# tiny85.net
KiCad netlist of a schematic drawn in EAGLE
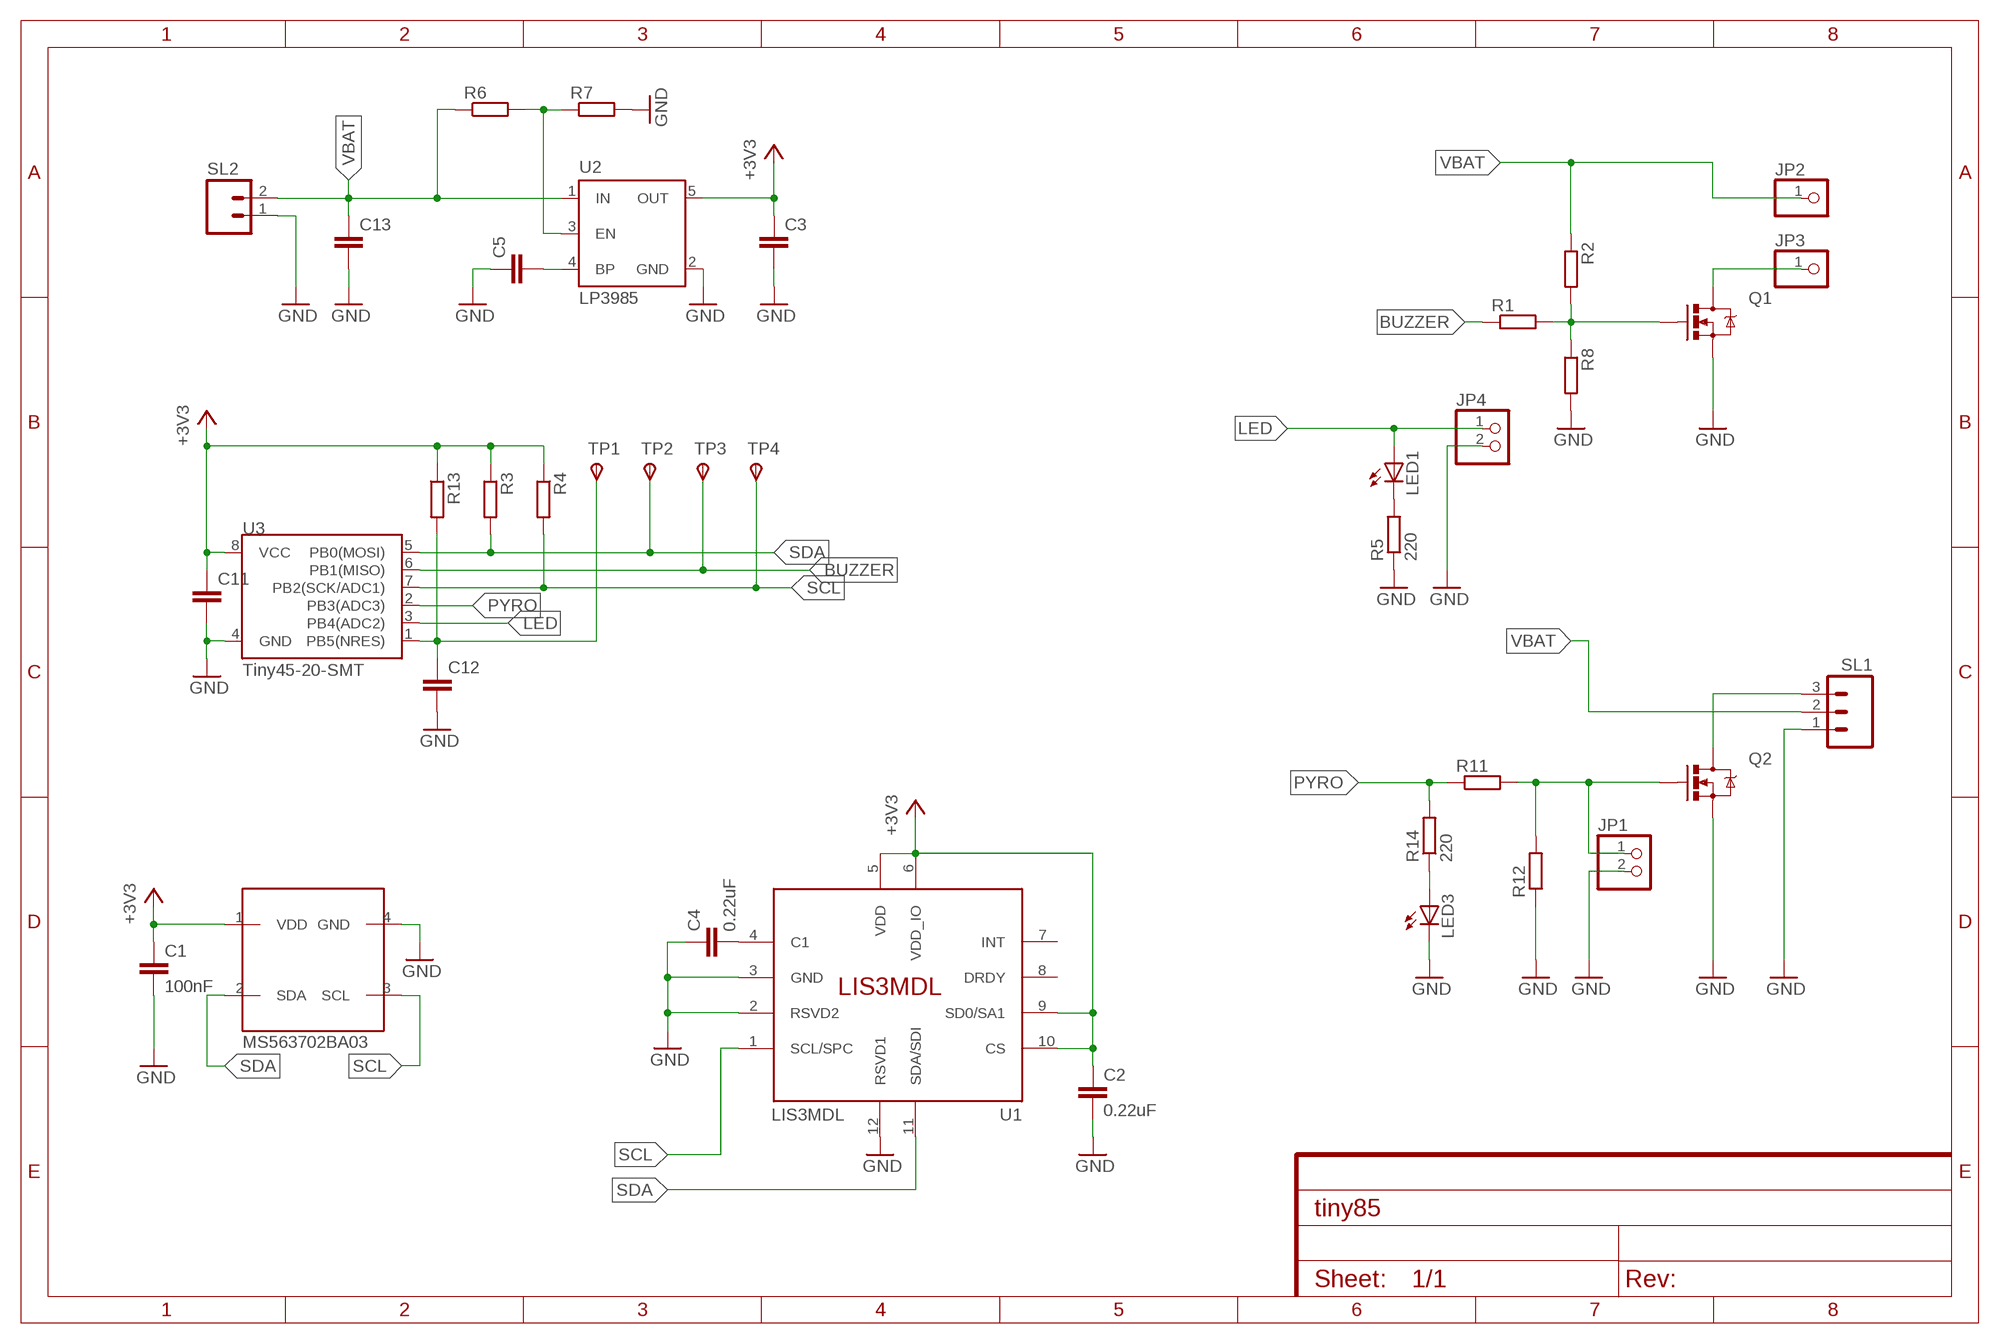
[diagram p0: schematic, sheet 1]

(export (version "E")
  (design (tool "Eeschema 10.0.6"))
  (components
    (comp (ref "C1")
      (value "100nF")
      (footprint "eagle-import:C0603")
      (libsource (lib "eagle-import") (part "C-EUC0603"))
    )
    (comp (ref "C2")
      (value "0.22uF")
      (footprint "eagle-import:C0603K")
      (libsource (lib "eagle-import") (part "C-EUC0603K"))
    )
    (comp (ref "C3")
      (value "C-EUC0603")
      (footprint "eagle-import:C0603")
      (libsource (lib "eagle-import") (part "C-EUC0603"))
    )
    (comp (ref "C4")
      (value "0.22uF")
      (footprint "eagle-import:C0603K")
      (libsource (lib "eagle-import") (part "C-EUC0603K"))
    )
    (comp (ref "C5")
      (value "C-EUC0603")
      (footprint "eagle-import:C0603")
      (libsource (lib "eagle-import") (part "C-EUC0603"))
    )
    (comp (ref "C11")
      (value "C-EUC0603")
      (footprint "eagle-import:C0603")
      (libsource (lib "eagle-import") (part "C-EUC0603"))
    )
    (comp (ref "C12")
      (value "C-EUC0603")
      (footprint "eagle-import:C0603")
      (libsource (lib "eagle-import") (part "C-EUC0603"))
    )
    (comp (ref "C13")
      (value "C-EUC0603")
      (footprint "eagle-import:C0603")
      (libsource (lib "eagle-import") (part "C-EUC0603"))
    )
    (comp (ref "IC1")
      (value "MS563702BA03")
      (footprint "eagle-import:MS5637")
      (libsource (lib "eagle-import") (part "MS563702BA03"))
    )
    (comp (ref "JP1")
      (value "PINHD-1X2")
      (footprint "eagle-import:1X02")
      (libsource (lib "eagle-import") (part "PINHD-1X2"))
    )
    (comp (ref "JP2")
      (value "PINHD-1X1")
      (footprint "eagle-import:1X01")
      (libsource (lib "eagle-import") (part "PINHD-1X1"))
    )
    (comp (ref "JP3")
      (value "PINHD-1X1")
      (footprint "eagle-import:1X01")
      (libsource (lib "eagle-import") (part "PINHD-1X1"))
    )
    (comp (ref "JP4")
      (value "PINHD-1X2")
      (footprint "eagle-import:1X02")
      (libsource (lib "eagle-import") (part "PINHD-1X2"))
    )
    (comp (ref "LED1")
      (value "LEDCHIPLED_0805")
      (footprint "eagle-import:CHIPLED_0805")
      (libsource (lib "eagle-import") (part "LEDCHIPLED_0805"))
    )
    (comp (ref "LED3")
      (value "LEDCHIPLED_0805")
      (footprint "eagle-import:CHIPLED_0805")
      (libsource (lib "eagle-import") (part "LEDCHIPLED_0805"))
    )
    (comp (ref "Q1")
      (value "MOSFET-NCHANNELBSS123LT1G")
      (footprint "eagle-import:SOT23-3")
      (libsource (lib "eagle-import") (part "MOSFET-NCHANNELBSS123LT1G"))
    )
    (comp (ref "Q2")
      (value "MOSFET-NCHANNELBSS123LT1G")
      (footprint "eagle-import:SOT23-3")
      (libsource (lib "eagle-import") (part "MOSFET-NCHANNELBSS123LT1G"))
    )
    (comp (ref "R1")
      (value "R-EU_R0603")
      (footprint "eagle-import:R0603")
      (libsource (lib "eagle-import") (part "R-EU_R0603"))
    )
    (comp (ref "R2")
      (value "R-EU_R0603")
      (footprint "eagle-import:R0603")
      (libsource (lib "eagle-import") (part "R-EU_R0603"))
    )
    (comp (ref "R3")
      (value "R-EU_R0603")
      (footprint "eagle-import:R0603")
      (libsource (lib "eagle-import") (part "R-EU_R0603"))
    )
    (comp (ref "R4")
      (value "R-EU_R0603")
      (footprint "eagle-import:R0603")
      (libsource (lib "eagle-import") (part "R-EU_R0603"))
    )
    (comp (ref "R5")
      (value "220")
      (footprint "eagle-import:R0603")
      (libsource (lib "eagle-import") (part "resistor_R-EU_R0603"))
    )
    (comp (ref "R6")
      (value "R-EU_R0603")
      (footprint "eagle-import:R0603")
      (libsource (lib "eagle-import") (part "R-EU_R0603"))
    )
    (comp (ref "R7")
      (value "R-EU_R0603")
      (footprint "eagle-import:R0603")
      (libsource (lib "eagle-import") (part "R-EU_R0603"))
    )
    (comp (ref "R8")
      (value "R-EU_R0603")
      (footprint "eagle-import:R0603")
      (libsource (lib "eagle-import") (part "R-EU_R0603"))
    )
    (comp (ref "R11")
      (value "R-EU_R0603")
      (footprint "eagle-import:R0603")
      (libsource (lib "eagle-import") (part "R-EU_R0603"))
    )
    (comp (ref "R12")
      (value "R-EU_R0603")
      (footprint "eagle-import:R0603")
      (libsource (lib "eagle-import") (part "R-EU_R0603"))
    )
    (comp (ref "R13")
      (value "R-EU_R0603")
      (footprint "eagle-import:R0603")
      (libsource (lib "eagle-import") (part "R-EU_R0603"))
    )
    (comp (ref "R14")
      (value "220")
      (footprint "eagle-import:R0603")
      (libsource (lib "eagle-import") (part "resistor_R-EU_R0603"))
    )
    (comp (ref "SL1")
      (value "M03")
      (footprint "eagle-import:03P")
      (libsource (lib "eagle-import") (part "M03"))
    )
    (comp (ref "SL2")
      (value "M02")
      (footprint "eagle-import:02P")
      (libsource (lib "eagle-import") (part "M02"))
    )
    (comp (ref "TP1")
      (value "TPSB1,27")
      (footprint "eagle-import:B1,27")
      (libsource (lib "eagle-import") (part "TPSB1,27"))
    )
    (comp (ref "TP2")
      (value "TPSB1,27")
      (footprint "eagle-import:B1,27")
      (libsource (lib "eagle-import") (part "TPSB1,27"))
    )
    (comp (ref "TP3")
      (value "TPSB1,27")
      (footprint "eagle-import:B1,27")
      (libsource (lib "eagle-import") (part "TPSB1,27"))
    )
    (comp (ref "TP4")
      (value "TPSB1,27")
      (footprint "eagle-import:B1,27")
      (libsource (lib "eagle-import") (part "TPSB1,27"))
    )
    (comp (ref "U1")
      (value "LIS3MDL")
      (footprint "eagle-import:VFLGA-12")
      (libsource (lib "eagle-import") (part "LIS3MDL"))
    )
    (comp (ref "U2")
      (value "LP3985")
      (footprint "eagle-import:SOT23-5")
      (libsource (lib "eagle-import") (part "VREG-5PIN-SOT23"))
    )
    (comp (ref "U3")
      (value "Tiny45-20-SMT")
      (footprint "eagle-import:SO08-EIAJ")
      (libsource (lib "eagle-import") (part "ATTINY45TINY45-20-SMT"))
    )
  )
  (nets
    (net (code "1") (name "+3V3") (class "Default")
      (node (ref "C1") (pin "1") (pinfunction "1_1") (pintype "passive"))
      (node (ref "C11") (pin "1") (pinfunction "1_1") (pintype "passive"))
      (node (ref "C2") (pin "1") (pinfunction "1_1") (pintype "passive"))
      (node (ref "C3") (pin "1") (pinfunction "1_1") (pintype "passive"))
      (node (ref "IC1") (pin "1") (pinfunction "VDD_1") (pintype "bidirectional"))
      (node (ref "R13") (pin "1") (pinfunction "1_1") (pintype "passive"))
      (node (ref "R3") (pin "1") (pinfunction "1_1") (pintype "passive"))
      (node (ref "R4") (pin "1") (pinfunction "1_1") (pintype "passive"))
      (node (ref "U1") (pin "10") (pinfunction "CS_10") (pintype "bidirectional"))
      (node (ref "U1") (pin "5") (pinfunction "VDD_5") (pintype "bidirectional"))
      (node (ref "U1") (pin "6") (pinfunction "VDD_IO_6") (pintype "power_in"))
      (node (ref "U1") (pin "9") (pinfunction "SD0/SA1_9") (pintype "bidirectional"))
      (node (ref "U2") (pin "5") (pinfunction "OUT_5") (pintype "bidirectional"))
      (node (ref "U3") (pin "8") (pinfunction "VCC_8") (pintype "bidirectional"))
    )
    (net (code "2") (name "BUZZER") (class "Default")
      (node (ref "R1") (pin "1") (pinfunction "1_1") (pintype "passive"))
      (node (ref "TP3") (pin "TP") (pinfunction "PP_TP") (pintype "input"))
      (node (ref "U3") (pin "6") (pinfunction "PB1(MISO)_6") (pintype "bidirectional"))
    )
    (net (code "3") (name "GND") (class "Default")
      (node (ref "C1") (pin "2") (pinfunction "2_2") (pintype "passive"))
      (node (ref "C11") (pin "2") (pinfunction "2_2") (pintype "passive"))
      (node (ref "C12") (pin "2") (pinfunction "2_2") (pintype "passive"))
      (node (ref "C13") (pin "2") (pinfunction "2_2") (pintype "passive"))
      (node (ref "C2") (pin "2") (pinfunction "2_2") (pintype "passive"))
      (node (ref "C3") (pin "2") (pinfunction "2_2") (pintype "passive"))
      (node (ref "C4") (pin "1") (pinfunction "1_1") (pintype "passive"))
      (node (ref "C5") (pin "1") (pinfunction "1_1") (pintype "passive"))
      (node (ref "IC1") (pin "4") (pinfunction "GND_4") (pintype "bidirectional"))
      (node (ref "JP1") (pin "2") (pinfunction "2_2") (pintype "passive"))
      (node (ref "JP4") (pin "2") (pinfunction "2_2") (pintype "passive"))
      (node (ref "LED3") (pin "C") (pinfunction "C_C") (pintype "passive"))
      (node (ref "Q1") (pin "2") (pinfunction "S_2") (pintype "passive"))
      (node (ref "Q2") (pin "2") (pinfunction "S_2") (pintype "passive"))
      (node (ref "R12") (pin "1") (pinfunction "1_1") (pintype "passive"))
      (node (ref "R5") (pin "1") (pinfunction "1_1") (pintype "passive"))
      (node (ref "R7") (pin "2") (pinfunction "2_2") (pintype "passive"))
      (node (ref "R8") (pin "2") (pinfunction "2_2") (pintype "passive"))
      (node (ref "SL1") (pin "1") (pinfunction "1_1") (pintype "passive"))
      (node (ref "SL2") (pin "1") (pinfunction "1_1") (pintype "passive"))
      (node (ref "U1") (pin "12") (pinfunction "RSVD1_12") (pintype "bidirectional"))
      (node (ref "U1") (pin "2") (pinfunction "RSVD2_2") (pintype "bidirectional"))
      (node (ref "U1") (pin "3") (pinfunction "GND_3") (pintype "power_in"))
      (node (ref "U2") (pin "2") (pinfunction "GND_2") (pintype "bidirectional"))
      (node (ref "U3") (pin "4") (pinfunction "GND_4") (pintype "bidirectional"))
    )
    (net (code "4") (name "LED") (class "Default")
      (node (ref "JP4") (pin "1") (pinfunction "1_1") (pintype "passive"))
      (node (ref "LED1") (pin "A") (pinfunction "A_A") (pintype "passive"))
      (node (ref "U3") (pin "3") (pinfunction "PB4(ADC2)_3") (pintype "bidirectional"))
    )
    (net (code "5") (name "Net-(LED1-PadC)") (class "Default")
      (node (ref "LED1") (pin "C") (pinfunction "C_C") (pintype "passive"))
      (node (ref "R5") (pin "2") (pinfunction "2_2") (pintype "passive"))
    )
    (net (code "6") (name "Net-(LED3-PadA)") (class "Default")
      (node (ref "LED3") (pin "A") (pinfunction "A_A") (pintype "passive"))
      (node (ref "R14") (pin "1") (pinfunction "1_1") (pintype "passive"))
    )
    (net (code "7") (name "Net-(Q1-D)") (class "Default")
      (node (ref "JP3") (pin "1") (pinfunction "1_1") (pintype "passive"))
      (node (ref "Q1") (pin "3") (pinfunction "D_3") (pintype "passive"))
    )
    (net (code "8") (name "Net-(Q1-G)") (class "Default")
      (node (ref "Q1") (pin "1") (pinfunction "G_1") (pintype "passive"))
      (node (ref "R1") (pin "2") (pinfunction "2_2") (pintype "passive"))
      (node (ref "R2") (pin "2") (pinfunction "2_2") (pintype "passive"))
      (node (ref "R8") (pin "1") (pinfunction "1_1") (pintype "passive"))
    )
    (net (code "9") (name "Net-(Q2-D)") (class "Default")
      (node (ref "Q2") (pin "3") (pinfunction "D_3") (pintype "passive"))
      (node (ref "SL1") (pin "3") (pinfunction "3_3") (pintype "passive"))
    )
    (net (code "10") (name "Net-(Q2-G)") (class "Default")
      (node (ref "JP1") (pin "1") (pinfunction "1_1") (pintype "passive"))
      (node (ref "Q2") (pin "1") (pinfunction "G_1") (pintype "passive"))
      (node (ref "R11") (pin "2") (pinfunction "2_2") (pintype "passive"))
      (node (ref "R12") (pin "2") (pinfunction "2_2") (pintype "passive"))
    )
    (net (code "11") (name "Net-(TP1-PP)") (class "Default")
      (node (ref "C12") (pin "1") (pinfunction "1_1") (pintype "passive"))
      (node (ref "R13") (pin "2") (pinfunction "2_2") (pintype "passive"))
      (node (ref "TP1") (pin "TP") (pinfunction "PP_TP") (pintype "input"))
      (node (ref "U3") (pin "1") (pinfunction "PB5(NRES)_1") (pintype "bidirectional"))
    )
    (net (code "12") (name "Net-(U1-C1)") (class "Default")
      (node (ref "C4") (pin "2") (pinfunction "2_2") (pintype "passive"))
      (node (ref "U1") (pin "4") (pinfunction "C1_4") (pintype "bidirectional"))
    )
    (net (code "13") (name "Net-(U2-BP)") (class "Default")
      (node (ref "C5") (pin "2") (pinfunction "2_2") (pintype "passive"))
      (node (ref "U2") (pin "4") (pinfunction "BP_4") (pintype "bidirectional"))
    )
    (net (code "14") (name "Net-(U2-EN)") (class "Default")
      (node (ref "R6") (pin "2") (pinfunction "2_2") (pintype "passive"))
      (node (ref "R7") (pin "1") (pinfunction "1_1") (pintype "passive"))
      (node (ref "U2") (pin "3") (pinfunction "EN_3") (pintype "bidirectional"))
    )
    (net (code "15") (name "PYRO") (class "Default")
      (node (ref "R11") (pin "1") (pinfunction "1_1") (pintype "passive"))
      (node (ref "R14") (pin "2") (pinfunction "2_2") (pintype "passive"))
      (node (ref "U3") (pin "2") (pinfunction "PB3(ADC3)_2") (pintype "bidirectional"))
    )
    (net (code "16") (name "SCL") (class "Default")
      (node (ref "IC1") (pin "3") (pinfunction "SCL_3") (pintype "bidirectional"))
      (node (ref "R4") (pin "2") (pinfunction "2_2") (pintype "passive"))
      (node (ref "TP4") (pin "TP") (pinfunction "PP_TP") (pintype "input"))
      (node (ref "U1") (pin "1") (pinfunction "SCL/SPC_1") (pintype "bidirectional"))
      (node (ref "U3") (pin "7") (pinfunction "PB2(SCK/ADC1)_7") (pintype "bidirectional"))
    )
    (net (code "17") (name "SDA") (class "Default")
      (node (ref "IC1") (pin "2") (pinfunction "SDA_2") (pintype "bidirectional"))
      (node (ref "R3") (pin "2") (pinfunction "2_2") (pintype "passive"))
      (node (ref "TP2") (pin "TP") (pinfunction "PP_TP") (pintype "input"))
      (node (ref "U1") (pin "11") (pinfunction "SDA/SDI_11") (pintype "bidirectional"))
      (node (ref "U3") (pin "5") (pinfunction "PB0(MOSI)_5") (pintype "bidirectional"))
    )
    (net (code "18") (name "VBAT") (class "Default")
      (node (ref "C13") (pin "1") (pinfunction "1_1") (pintype "passive"))
      (node (ref "JP2") (pin "1") (pinfunction "1_1") (pintype "passive"))
      (node (ref "R2") (pin "1") (pinfunction "1_1") (pintype "passive"))
      (node (ref "R6") (pin "1") (pinfunction "1_1") (pintype "passive"))
      (node (ref "SL1") (pin "2") (pinfunction "2_2") (pintype "passive"))
      (node (ref "SL2") (pin "2") (pinfunction "2_2") (pintype "passive"))
      (node (ref "U2") (pin "1") (pinfunction "IN_1") (pintype "bidirectional"))
    )
    (net (code "19") (name "unconnected-(U1-DRDY-Pad8)") (class "Default")
      (node (ref "U1") (pin "8") (pinfunction "DRDY_8") (pintype "bidirectional"))
    )
    (net (code "20") (name "unconnected-(U1-INT-Pad7)") (class "Default")
      (node (ref "U1") (pin "7") (pinfunction "INT_7") (pintype "bidirectional"))
    )
  )
)
